# iPhone11ProMaxWAII.net
KiCad netlist of a schematic drawn in Altium Designer
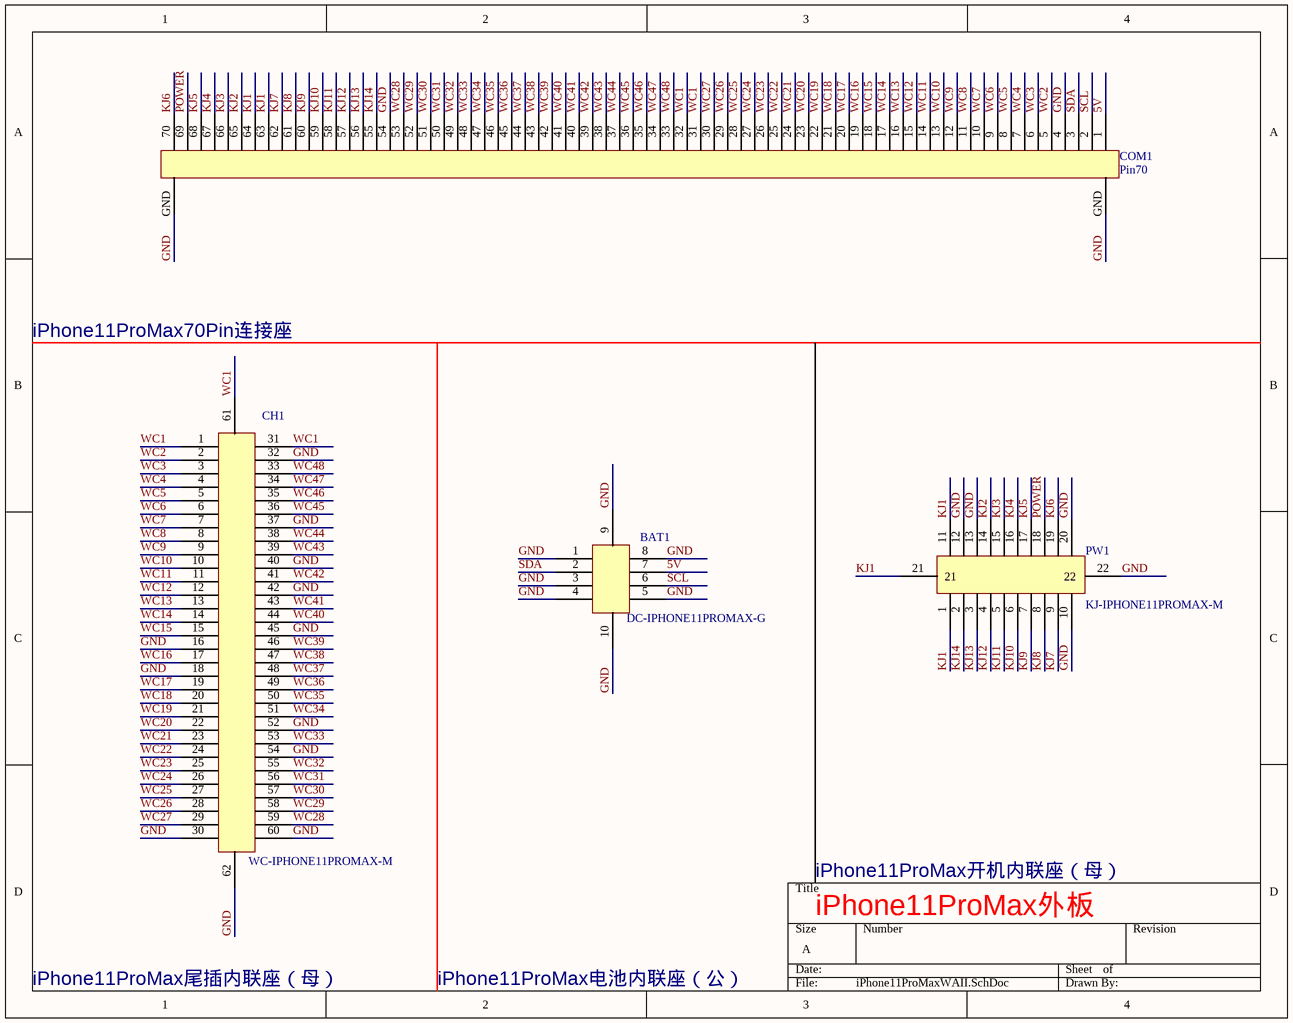
[diagram p0: iPhone11ProMaxWAII.SchDoc]

(export (version "E")
  (design (tool "Eeschema 10.0.6"))
  (components
    (comp (ref "BAT1")
      (value "DC-IPHONE11PROMAX-G")
      (footprint "IPHONE11-WXCD-G")
      (libsource (lib "iPhone") (part "WXCD-IPHONE11-G"))
    )
    (comp (ref "CH1")
      (value "WC-IPHONE11PROMAX-M")
      (footprint "IPHONE11PROMAX-WC-M")
      (libsource (lib "iPhone") (part "WC-IPHONE11PROMAX-M"))
    )
    (comp (ref "COM1") (value "Pin70") (footprint "Pin70") (libsource (lib "iPhone") (part "Pin70")))
    (comp (ref "PW1")
      (value "KJ-IPHONE11PROMAX-M")
      (footprint "IPHONE11PROMAX-KJ-M")
      (libsource (lib "iPhone") (part "KJ-IPHONE11PROMAX-M"))
    )
  )
  (nets
    (net (code "1") (name "/5V") (class "Default")
      (node (ref "BAT1") (pin "7") (pintype "passive"))
      (node (ref "COM1") (pin "1") (pintype "passive"))
    )
    (net (code "2") (name "/GND") (class "Default")
      (node (ref "BAT1") (pin "1") (pintype "passive"))
      (node (ref "BAT1") (pin "10") (pintype "passive"))
      (node (ref "BAT1") (pin "3") (pintype "passive"))
      (node (ref "BAT1") (pin "4") (pintype "passive"))
      (node (ref "BAT1") (pin "5") (pintype "passive"))
      (node (ref "BAT1") (pin "8") (pintype "passive"))
      (node (ref "BAT1") (pin "9") (pintype "passive"))
      (node (ref "CH1") (pin "16") (pintype "passive"))
      (node (ref "CH1") (pin "18") (pintype "passive"))
      (node (ref "CH1") (pin "30") (pintype "passive"))
      (node (ref "CH1") (pin "32") (pintype "passive"))
      (node (ref "CH1") (pin "37") (pintype "passive"))
      (node (ref "CH1") (pin "40") (pintype "passive"))
      (node (ref "CH1") (pin "42") (pintype "passive"))
      (node (ref "CH1") (pin "45") (pintype "passive"))
      (node (ref "CH1") (pin "52") (pintype "passive"))
      (node (ref "CH1") (pin "54") (pintype "passive"))
      (node (ref "CH1") (pin "60") (pintype "passive"))
      (node (ref "CH1") (pin "62") (pintype "passive"))
      (node (ref "COM1") (pin "4") (pintype "passive"))
      (node (ref "COM1") (pin "54") (pintype "passive"))
      (node (ref "COM1") (pin "GND") (pintype "passive"))
      (node (ref "PW1") (pin "10") (pintype "passive"))
      (node (ref "PW1") (pin "12") (pintype "passive"))
      (node (ref "PW1") (pin "13") (pintype "passive"))
      (node (ref "PW1") (pin "20") (pintype "passive"))
      (node (ref "PW1") (pin "22") (pinfunction "22_22") (pintype "passive"))
    )
    (net (code "3") (name "/KJ1") (class "Default")
      (node (ref "COM1") (pin "63") (pintype "passive"))
      (node (ref "COM1") (pin "64") (pintype "passive"))
      (node (ref "PW1") (pin "1") (pintype "passive"))
      (node (ref "PW1") (pin "11") (pintype "passive"))
      (node (ref "PW1") (pin "21") (pinfunction "21_21") (pintype "passive"))
    )
    (net (code "4") (name "/KJ2") (class "Default")
      (node (ref "COM1") (pin "65") (pintype "passive"))
      (node (ref "PW1") (pin "14") (pintype "passive"))
    )
    (net (code "5") (name "/KJ3") (class "Default")
      (node (ref "COM1") (pin "66") (pintype "passive"))
      (node (ref "PW1") (pin "15") (pintype "passive"))
    )
    (net (code "6") (name "/KJ4") (class "Default")
      (node (ref "COM1") (pin "67") (pintype "passive"))
      (node (ref "PW1") (pin "16") (pintype "passive"))
    )
    (net (code "7") (name "/KJ5") (class "Default")
      (node (ref "COM1") (pin "68") (pintype "passive"))
      (node (ref "PW1") (pin "17") (pintype "passive"))
    )
    (net (code "8") (name "/KJ6") (class "Default")
      (node (ref "COM1") (pin "70") (pintype "passive"))
      (node (ref "PW1") (pin "19") (pintype "passive"))
    )
    (net (code "9") (name "/KJ7") (class "Default")
      (node (ref "COM1") (pin "62") (pintype "passive"))
      (node (ref "PW1") (pin "9") (pintype "passive"))
    )
    (net (code "10") (name "/KJ8") (class "Default")
      (node (ref "COM1") (pin "61") (pintype "passive"))
      (node (ref "PW1") (pin "8") (pintype "passive"))
    )
    (net (code "11") (name "/KJ9") (class "Default")
      (node (ref "COM1") (pin "60") (pintype "passive"))
      (node (ref "PW1") (pin "7") (pintype "passive"))
    )
    (net (code "12") (name "/KJ10") (class "Default")
      (node (ref "COM1") (pin "59") (pintype "passive"))
      (node (ref "PW1") (pin "6") (pintype "passive"))
    )
    (net (code "13") (name "/KJ11") (class "Default")
      (node (ref "COM1") (pin "58") (pintype "passive"))
      (node (ref "PW1") (pin "5") (pintype "passive"))
    )
    (net (code "14") (name "/KJ12") (class "Default")
      (node (ref "COM1") (pin "57") (pintype "passive"))
      (node (ref "PW1") (pin "4") (pintype "passive"))
    )
    (net (code "15") (name "/KJ13") (class "Default")
      (node (ref "COM1") (pin "56") (pintype "passive"))
      (node (ref "PW1") (pin "3") (pintype "passive"))
    )
    (net (code "16") (name "/KJ14") (class "Default")
      (node (ref "COM1") (pin "55") (pintype "passive"))
      (node (ref "PW1") (pin "2") (pintype "passive"))
    )
    (net (code "17") (name "/POWER") (class "Default")
      (node (ref "COM1") (pin "69") (pintype "passive"))
      (node (ref "PW1") (pin "18") (pintype "passive"))
    )
    (net (code "18") (name "/SCL") (class "Default")
      (node (ref "BAT1") (pin "6") (pintype "passive"))
      (node (ref "COM1") (pin "2") (pintype "passive"))
    )
    (net (code "19") (name "/SDA") (class "Default")
      (node (ref "BAT1") (pin "2") (pintype "passive"))
      (node (ref "COM1") (pin "3") (pintype "passive"))
    )
    (net (code "20") (name "/WC1") (class "Default")
      (node (ref "CH1") (pin "1") (pintype "passive"))
      (node (ref "CH1") (pin "31") (pintype "passive"))
      (node (ref "CH1") (pin "61") (pintype "passive"))
      (node (ref "COM1") (pin "31") (pintype "passive"))
      (node (ref "COM1") (pin "32") (pintype "passive"))
    )
    (net (code "21") (name "/WC2") (class "Default")
      (node (ref "CH1") (pin "2") (pintype "passive"))
      (node (ref "COM1") (pin "5") (pintype "passive"))
    )
    (net (code "22") (name "/WC3") (class "Default")
      (node (ref "CH1") (pin "3") (pintype "passive"))
      (node (ref "COM1") (pin "6") (pintype "passive"))
    )
    (net (code "23") (name "/WC4") (class "Default")
      (node (ref "CH1") (pin "4") (pintype "passive"))
      (node (ref "COM1") (pin "7") (pintype "passive"))
    )
    (net (code "24") (name "/WC5") (class "Default")
      (node (ref "CH1") (pin "5") (pintype "passive"))
      (node (ref "COM1") (pin "8") (pintype "passive"))
    )
    (net (code "25") (name "/WC6") (class "Default")
      (node (ref "CH1") (pin "6") (pintype "passive"))
      (node (ref "COM1") (pin "9") (pintype "passive"))
    )
    (net (code "26") (name "/WC7") (class "Default")
      (node (ref "CH1") (pin "7") (pintype "passive"))
      (node (ref "COM1") (pin "10") (pintype "passive"))
    )
    (net (code "27") (name "/WC8") (class "Default")
      (node (ref "CH1") (pin "8") (pintype "passive"))
      (node (ref "COM1") (pin "11") (pintype "passive"))
    )
    (net (code "28") (name "/WC9") (class "Default")
      (node (ref "CH1") (pin "9") (pintype "passive"))
      (node (ref "COM1") (pin "12") (pintype "passive"))
    )
    (net (code "29") (name "/WC10") (class "Default")
      (node (ref "CH1") (pin "10") (pintype "passive"))
      (node (ref "COM1") (pin "13") (pintype "passive"))
    )
    (net (code "30") (name "/WC11") (class "Default")
      (node (ref "CH1") (pin "11") (pintype "passive"))
      (node (ref "COM1") (pin "14") (pintype "passive"))
    )
    (net (code "31") (name "/WC12") (class "Default")
      (node (ref "CH1") (pin "12") (pintype "passive"))
      (node (ref "COM1") (pin "15") (pintype "passive"))
    )
    (net (code "32") (name "/WC13") (class "Default")
      (node (ref "CH1") (pin "13") (pintype "passive"))
      (node (ref "COM1") (pin "16") (pintype "passive"))
    )
    (net (code "33") (name "/WC14") (class "Default")
      (node (ref "CH1") (pin "14") (pintype "passive"))
      (node (ref "COM1") (pin "17") (pintype "passive"))
    )
    (net (code "34") (name "/WC15") (class "Default")
      (node (ref "CH1") (pin "15") (pintype "passive"))
      (node (ref "COM1") (pin "18") (pintype "passive"))
    )
    (net (code "35") (name "/WC16") (class "Default")
      (node (ref "CH1") (pin "17") (pintype "passive"))
      (node (ref "COM1") (pin "19") (pintype "passive"))
    )
    (net (code "36") (name "/WC17") (class "Default")
      (node (ref "CH1") (pin "19") (pintype "passive"))
      (node (ref "COM1") (pin "20") (pintype "passive"))
    )
    (net (code "37") (name "/WC18") (class "Default")
      (node (ref "CH1") (pin "20") (pintype "passive"))
      (node (ref "COM1") (pin "21") (pintype "passive"))
    )
    (net (code "38") (name "/WC19") (class "Default")
      (node (ref "CH1") (pin "21") (pintype "passive"))
      (node (ref "COM1") (pin "22") (pintype "passive"))
    )
    (net (code "39") (name "/WC20") (class "Default")
      (node (ref "CH1") (pin "22") (pintype "passive"))
      (node (ref "COM1") (pin "23") (pintype "passive"))
    )
    (net (code "40") (name "/WC21") (class "Default")
      (node (ref "CH1") (pin "23") (pintype "passive"))
      (node (ref "COM1") (pin "24") (pintype "passive"))
    )
    (net (code "41") (name "/WC22") (class "Default")
      (node (ref "CH1") (pin "24") (pintype "passive"))
      (node (ref "COM1") (pin "25") (pintype "passive"))
    )
    (net (code "42") (name "/WC23") (class "Default")
      (node (ref "CH1") (pin "25") (pintype "passive"))
      (node (ref "COM1") (pin "26") (pintype "passive"))
    )
    (net (code "43") (name "/WC24") (class "Default")
      (node (ref "CH1") (pin "26") (pintype "passive"))
      (node (ref "COM1") (pin "27") (pintype "passive"))
    )
    (net (code "44") (name "/WC25") (class "Default")
      (node (ref "CH1") (pin "27") (pintype "passive"))
      (node (ref "COM1") (pin "28") (pintype "passive"))
    )
    (net (code "45") (name "/WC26") (class "Default")
      (node (ref "CH1") (pin "28") (pintype "passive"))
      (node (ref "COM1") (pin "29") (pintype "passive"))
    )
    (net (code "46") (name "/WC27") (class "Default")
      (node (ref "CH1") (pin "29") (pintype "passive"))
      (node (ref "COM1") (pin "30") (pintype "passive"))
    )
    (net (code "47") (name "/WC28") (class "Default")
      (node (ref "CH1") (pin "59") (pintype "passive"))
      (node (ref "COM1") (pin "53") (pintype "passive"))
    )
    (net (code "48") (name "/WC29") (class "Default")
      (node (ref "CH1") (pin "58") (pintype "passive"))
      (node (ref "COM1") (pin "52") (pintype "passive"))
    )
    (net (code "49") (name "/WC30") (class "Default")
      (node (ref "CH1") (pin "57") (pintype "passive"))
      (node (ref "COM1") (pin "51") (pintype "passive"))
    )
    (net (code "50") (name "/WC31") (class "Default")
      (node (ref "CH1") (pin "56") (pintype "passive"))
      (node (ref "COM1") (pin "50") (pintype "passive"))
    )
    (net (code "51") (name "/WC32") (class "Default")
      (node (ref "CH1") (pin "55") (pintype "passive"))
      (node (ref "COM1") (pin "49") (pintype "passive"))
    )
    (net (code "52") (name "/WC33") (class "Default")
      (node (ref "CH1") (pin "53") (pintype "passive"))
      (node (ref "COM1") (pin "48") (pintype "passive"))
    )
    (net (code "53") (name "/WC34") (class "Default")
      (node (ref "CH1") (pin "51") (pintype "passive"))
      (node (ref "COM1") (pin "47") (pintype "passive"))
    )
    (net (code "54") (name "/WC35") (class "Default")
      (node (ref "CH1") (pin "50") (pintype "passive"))
      (node (ref "COM1") (pin "46") (pintype "passive"))
    )
    (net (code "55") (name "/WC36") (class "Default")
      (node (ref "CH1") (pin "49") (pintype "passive"))
      (node (ref "COM1") (pin "45") (pintype "passive"))
    )
    (net (code "56") (name "/WC37") (class "Default")
      (node (ref "CH1") (pin "48") (pintype "passive"))
      (node (ref "COM1") (pin "44") (pintype "passive"))
    )
    (net (code "57") (name "/WC38") (class "Default")
      (node (ref "CH1") (pin "47") (pintype "passive"))
      (node (ref "COM1") (pin "43") (pintype "passive"))
    )
    (net (code "58") (name "/WC39") (class "Default")
      (node (ref "CH1") (pin "46") (pintype "passive"))
      (node (ref "COM1") (pin "42") (pintype "passive"))
    )
    (net (code "59") (name "/WC40") (class "Default")
      (node (ref "CH1") (pin "44") (pintype "passive"))
      (node (ref "COM1") (pin "41") (pintype "passive"))
    )
    (net (code "60") (name "/WC41") (class "Default")
      (node (ref "CH1") (pin "43") (pintype "passive"))
      (node (ref "COM1") (pin "40") (pintype "passive"))
    )
    (net (code "61") (name "/WC42") (class "Default")
      (node (ref "CH1") (pin "41") (pintype "passive"))
      (node (ref "COM1") (pin "39") (pintype "passive"))
    )
    (net (code "62") (name "/WC43") (class "Default")
      (node (ref "CH1") (pin "39") (pintype "passive"))
      (node (ref "COM1") (pin "38") (pintype "passive"))
    )
    (net (code "63") (name "/WC44") (class "Default")
      (node (ref "CH1") (pin "38") (pintype "passive"))
      (node (ref "COM1") (pin "37") (pintype "passive"))
    )
    (net (code "64") (name "/WC45") (class "Default")
      (node (ref "CH1") (pin "36") (pintype "passive"))
      (node (ref "COM1") (pin "36") (pintype "passive"))
    )
    (net (code "65") (name "/WC46") (class "Default")
      (node (ref "CH1") (pin "35") (pintype "passive"))
      (node (ref "COM1") (pin "35") (pintype "passive"))
    )
    (net (code "66") (name "/WC47") (class "Default")
      (node (ref "CH1") (pin "34") (pintype "passive"))
      (node (ref "COM1") (pin "34") (pintype "passive"))
    )
    (net (code "67") (name "/WC48") (class "Default")
      (node (ref "CH1") (pin "33") (pintype "passive"))
      (node (ref "COM1") (pin "33") (pintype "passive"))
    )
  )
)
